# iTimeAfrica.net
KiCad netlist of a schematic drawn in Altium Designer
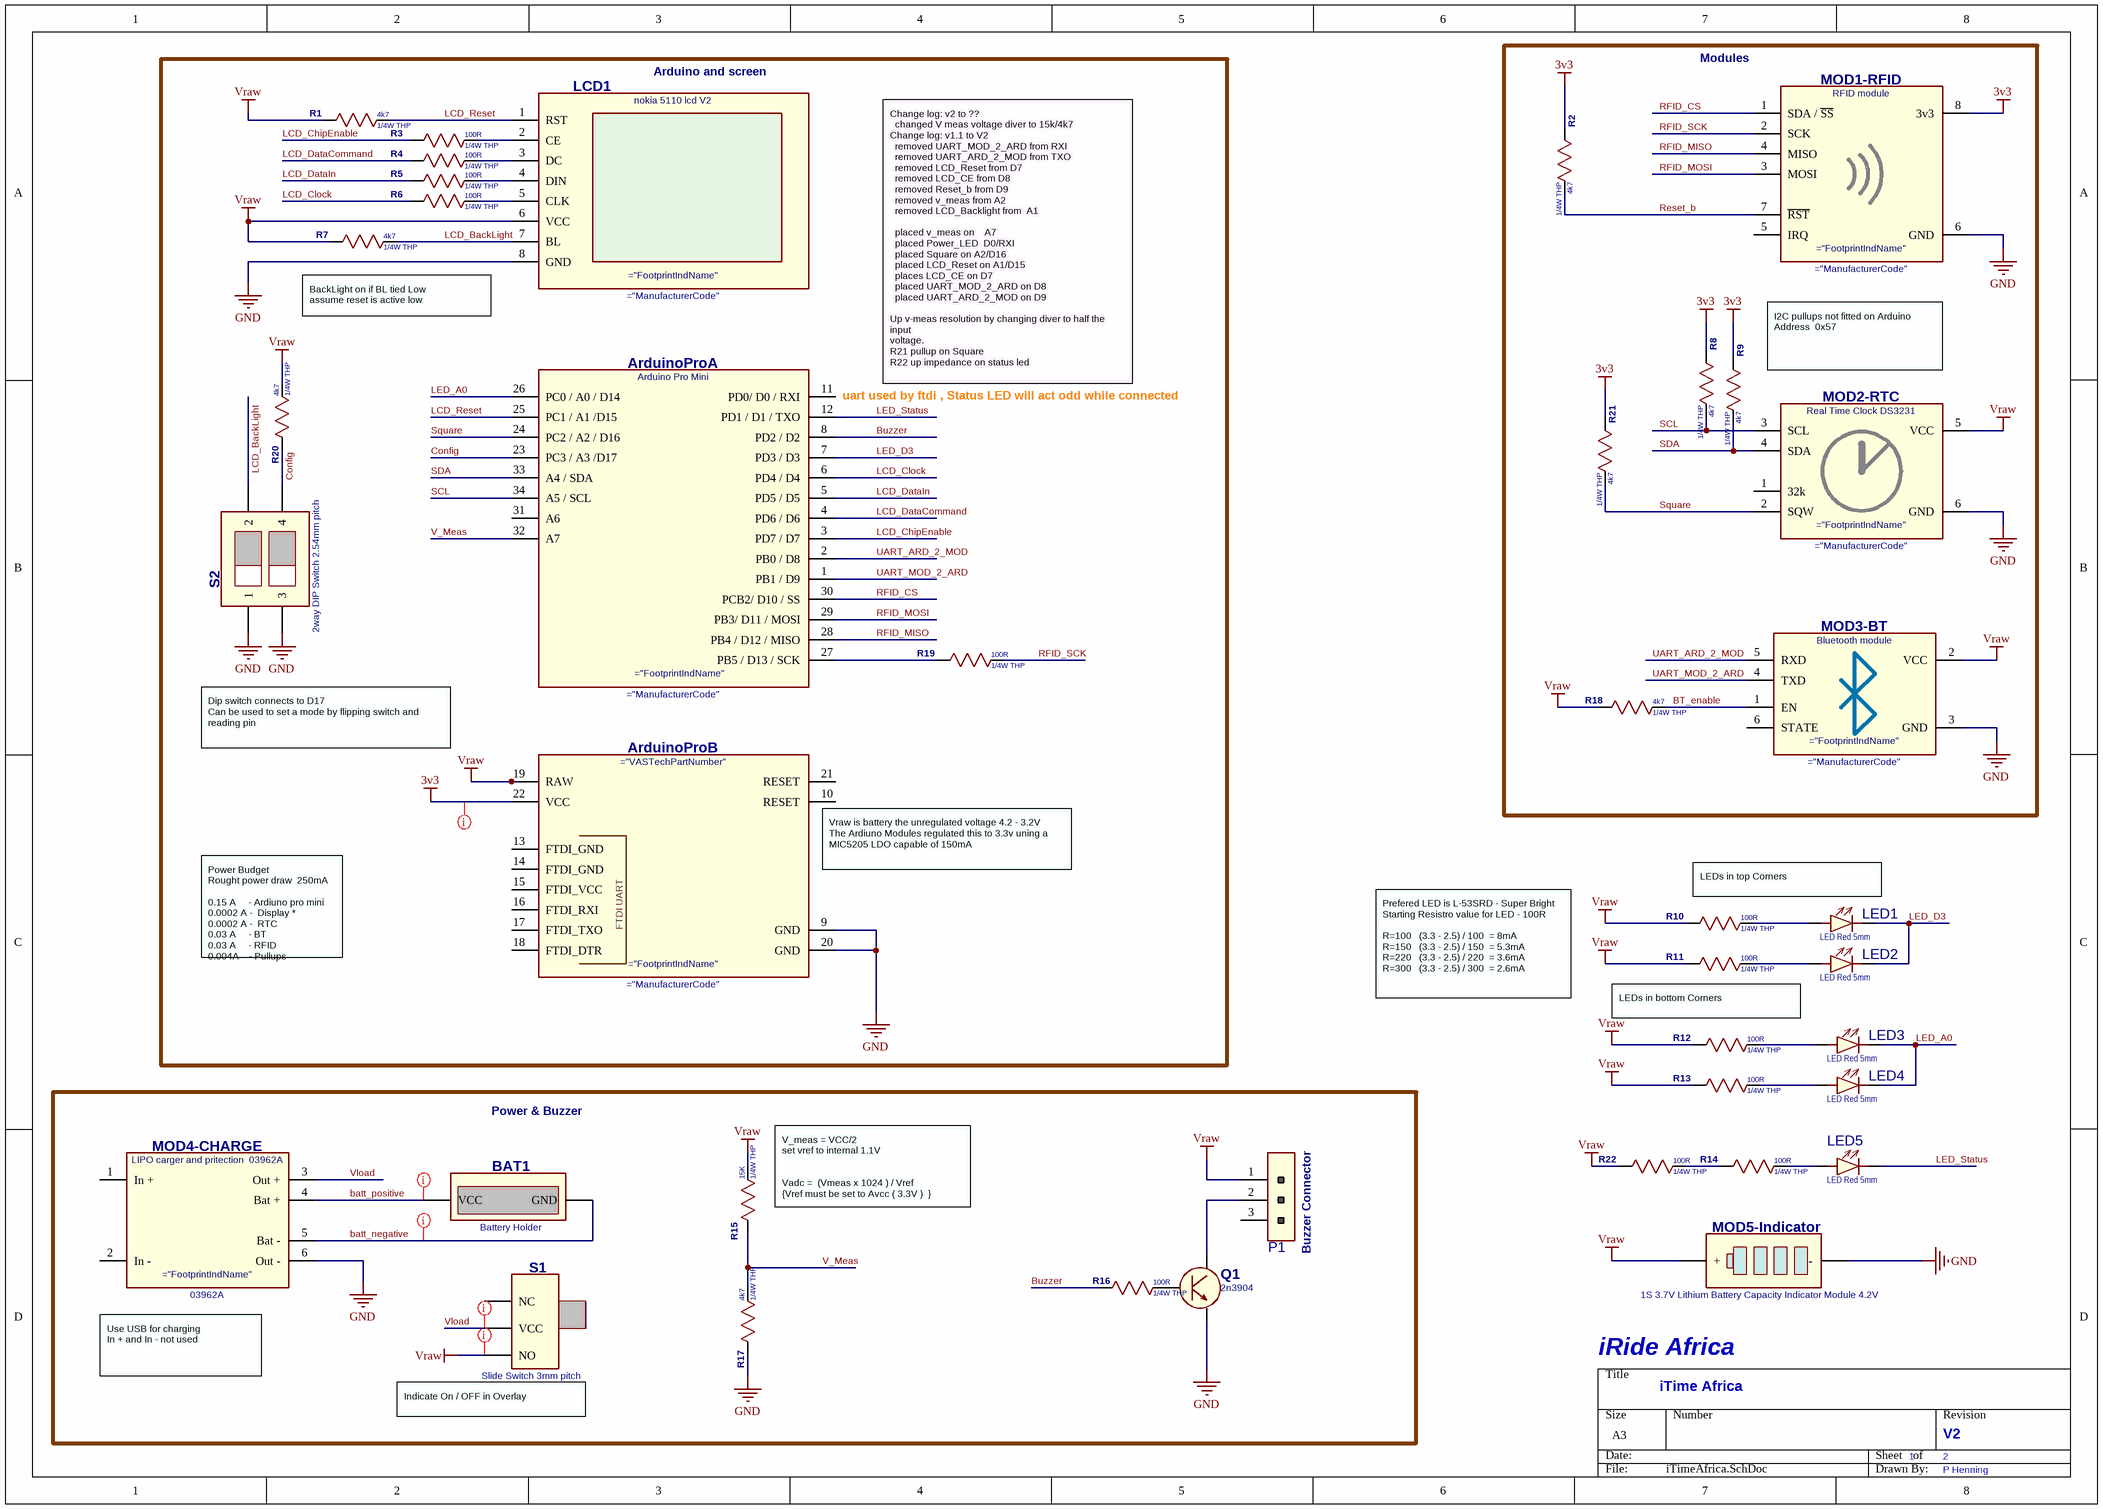
[diagram p0: iTimeAfrica.SchDoc]

(export (version "E")
  (design (tool "Eeschema 10.0.6"))
  (components
    (comp (ref "ArduinoPro")
      (value "Arduino Pro Mini")
      (footprint "ARDUINO PRO MINI v2 (NO FTDI)")
      (fields
        (field (name "MANUFACTURER") "SparkFun Electronics")
        (field (name "MANUFACTURERPARTNUMBER") "DEV-11113  (check this)")
      )
      (libsource (lib "Copy of Undero_Symbols_v7") (part "Arduino Pro Mini"))
    )
    (comp (ref "BAT1")
      (value "Battery Holder")
      (footprint "Battery Holder")
      (libsource (lib "Copy of Undero_Symbols_v7") (part "Battery Holder"))
    )
    (comp (ref "LCD1")
      (value "nokia 5110 lcd")
      (footprint "Nokia 5110 GLCD 84x48")
      (description "nokia 5110 lcd V2")
      (fields (field (name "MANUFACTURER") "unknown"))
      (libsource (lib "Copy of Undero_Symbols_v7") (part "nokia 5110 lcd V2"))
    )
    (comp (ref "LED1")
      (value "LED Red 5mm")
      (footprint "LED THL 5x9mm Vert")
      (description "Red LED, 5mm THP")
      (fields
        (field (name "MANUFACTURERPARTNUMBER") "L-53SR")
        (field (name "MANUFACTURER") "kingbright")
        (field (name "ATTRIBUTES") "LED Red 5mm")
      )
      (libsource (lib "Copy of Undero_Symbols_v7") (part "Red LED THP"))
    )
    (comp (ref "LED2")
      (value "LED Red 5mm")
      (footprint "LED THL 5x9mm Vert")
      (description "Red LED, 5mm THP")
      (fields
        (field (name "MANUFACTURERPARTNUMBER") "L-53SR")
        (field (name "MANUFACTURER") "kingbright")
        (field (name "ATTRIBUTES") "LED Red 5mm")
      )
      (libsource (lib "Copy of Undero_Symbols_v7") (part "Red LED THP"))
    )
    (comp (ref "LED3")
      (value "LED Red 5mm")
      (footprint "LED THL 5x9mm Vert")
      (description "Red LED, 5mm THP")
      (fields
        (field (name "MANUFACTURERPARTNUMBER") "L-53SR")
        (field (name "MANUFACTURER") "kingbright")
        (field (name "ATTRIBUTES") "LED Red 5mm")
      )
      (libsource (lib "Copy of Undero_Symbols_v7") (part "Red LED THP"))
    )
    (comp (ref "LED4")
      (value "LED Red 5mm")
      (footprint "LED THL 5x9mm Vert")
      (description "Red LED, 5mm THP")
      (fields
        (field (name "MANUFACTURERPARTNUMBER") "L-53SR")
        (field (name "MANUFACTURER") "kingbright")
        (field (name "ATTRIBUTES") "LED Red 5mm")
      )
      (libsource (lib "Copy of Undero_Symbols_v7") (part "Red LED THP"))
    )
    (comp (ref "LED5")
      (value "LED Red 5mm")
      (footprint "LED THL 5x9mm Vert")
      (description "Red LED, 5mm THP")
      (fields
        (field (name "MANUFACTURERPARTNUMBER") "L-53SR")
        (field (name "MANUFACTURER") "kingbright")
        (field (name "ATTRIBUTES") "LED Red 5mm")
      )
      (libsource (lib "Copy of Undero_Symbols_v7") (part "Red LED THP"))
    )
    (comp (ref "MOD1-RFID")
      (value "RFID module")
      (footprint "RFID-RC522 (2 MH)")
      (fields (field (name "MANUFACTURERPARTNUMBER") "RFID-RC533"))
      (libsource (lib "Copy of Undero_Symbols_v7") (part "RFID module"))
    )
    (comp (ref "MOD2-RTC")
      (value "Real Time Clock DS3231")
      (footprint "RTC DS3231 (2 MH)")
      (libsource (lib "Copy of Undero_Symbols_v7") (part "Real Time Clock DS3231"))
    )
    (comp (ref "MOD3-BT")
      (value "Bluetooth module")
      (footprint "BlueTooth Card")
      (libsource (lib "Copy of Undero_Symbols_v7") (part "Bluetooth module"))
    )
    (comp (ref "MOD4-CHARGE")
      (value "Real Time Clock DS3231")
      (footprint "Charger/protection")
      (description "LIPO carger and pritection  03962A")
      (fields (field (name "MANUFACTURERPARTNUMBER") "03962A"))
      (libsource (lib "iTimeAfrica_Symbol") (part "Charger / Protection"))
    )
    (comp (ref "MOD5-Indicator")
      (value "1S 3.7V Lithium Battery Capacity Indicator Module 4.2V")
      (footprint "Battery Indicator  single mouning hole")
      (libsource (lib "Copy of Undero_Symbols_v7") (part "Battery Indicator"))
    )
    (comp (ref "P1")
      (value "3 pin Screw Terminal 3.5mm")
      (footprint "3x1 Screw terminal 3.5mm")
      (fields (field (name "MANUFACTURERPARTNUMBER") "1984950") (field (name "MANUFACTURER") "RS"))
      (libsource (lib "Copy of Undero_Symbols_v7") (part "3 pin Screw Terminal 3.5mm"))
    )
    (comp (ref "Q1")
      (value "2n3904")
      (footprint "TO-92")
      (description "NPN Transistor")
      (fields (field (name "MANUFACTURER") "Fairchild") (field (name "ATTRIBUTES") "2n3904"))
      (libsource (lib "Copy of Undero_Symbols_v7") (part "NPN Transistor"))
    )
    (comp (ref "R1")
      (value "4k7")
      (footprint "Res 1/4W THP (4k7)")
      (description "Resistor")
      (fields (field (name "PACKAGE") "1/4W THP") (field (name "ATTRIBUTES") "4k7"))
      (libsource (lib "iTimeAfrica_Symbol") (part "4k7"))
    )
    (comp (ref "R2")
      (value "4k7")
      (footprint "Res 1/4W THP (4k7)")
      (description "Resistor")
      (fields (field (name "PACKAGE") "1/4W THP") (field (name "ATTRIBUTES") "4k7"))
      (libsource (lib "iTimeAfrica_Symbol") (part "4k7"))
    )
    (comp (ref "R3")
      (value "100R")
      (footprint "Res 1/4W THP (100R)")
      (description "Resistor")
      (fields (field (name "PACKAGE") "1/4W THP") (field (name "ATTRIBUTES") "100R"))
      (libsource (lib "iTimeAfrica_Symbol") (part "100R"))
    )
    (comp (ref "R4")
      (value "100R")
      (footprint "Res 1/4W THP (100R)")
      (description "Resistor")
      (fields (field (name "PACKAGE") "1/4W THP") (field (name "ATTRIBUTES") "100R"))
      (libsource (lib "iTimeAfrica_Symbol") (part "100R"))
    )
    (comp (ref "R5")
      (value "100R")
      (footprint "Res 1/4W THP (100R)")
      (description "Resistor")
      (fields (field (name "PACKAGE") "1/4W THP") (field (name "ATTRIBUTES") "100R"))
      (libsource (lib "iTimeAfrica_Symbol") (part "100R"))
    )
    (comp (ref "R6")
      (value "100R")
      (footprint "Res 1/4W THP (100R)")
      (description "Resistor")
      (fields (field (name "PACKAGE") "1/4W THP") (field (name "ATTRIBUTES") "100R"))
      (libsource (lib "iTimeAfrica_Symbol") (part "100R"))
    )
    (comp (ref "R7")
      (value "4k7")
      (footprint "Res 1/4W THP (4k7)")
      (description "Resistor")
      (fields (field (name "PACKAGE") "1/4W THP") (field (name "ATTRIBUTES") "4k7"))
      (libsource (lib "iTimeAfrica_Symbol") (part "4k7"))
    )
    (comp (ref "R8")
      (value "4k7")
      (footprint "Res 1/4W THP (4k7)")
      (description "Resistor")
      (fields (field (name "PACKAGE") "1/4W THP") (field (name "ATTRIBUTES") "4k7"))
      (libsource (lib "iTimeAfrica_Symbol") (part "4k7"))
    )
    (comp (ref "R9")
      (value "4k7")
      (footprint "Res 1/4W THP (4k7)")
      (description "Resistor")
      (fields (field (name "PACKAGE") "1/4W THP") (field (name "ATTRIBUTES") "4k7"))
      (libsource (lib "iTimeAfrica_Symbol") (part "4k7"))
    )
    (comp (ref "R10")
      (value "100R")
      (footprint "Res 1/4W THP (100R)")
      (description "Resistor")
      (fields (field (name "PACKAGE") "1/4W THP") (field (name "ATTRIBUTES") "100R"))
      (libsource (lib "iTimeAfrica_Symbol") (part "100R"))
    )
    (comp (ref "R11")
      (value "100R")
      (footprint "Res 1/4W THP (100R)")
      (description "Resistor")
      (fields (field (name "PACKAGE") "1/4W THP") (field (name "ATTRIBUTES") "100R"))
      (libsource (lib "iTimeAfrica_Symbol") (part "100R"))
    )
    (comp (ref "R12")
      (value "100R")
      (footprint "Res 1/4W THP (100R)")
      (description "Resistor")
      (fields (field (name "PACKAGE") "1/4W THP") (field (name "ATTRIBUTES") "100R"))
      (libsource (lib "iTimeAfrica_Symbol") (part "100R"))
    )
    (comp (ref "R13")
      (value "100R")
      (footprint "Res 1/4W THP (100R)")
      (description "Resistor")
      (fields (field (name "PACKAGE") "1/4W THP") (field (name "ATTRIBUTES") "100R"))
      (libsource (lib "iTimeAfrica_Symbol") (part "100R"))
    )
    (comp (ref "R14")
      (value "100R")
      (footprint "Res 1/4W THP (100R)")
      (description "Resistor")
      (fields (field (name "PACKAGE") "1/4W THP") (field (name "ATTRIBUTES") "100R"))
      (libsource (lib "iTimeAfrica_Symbol") (part "100R"))
    )
    (comp (ref "R15")
      (value "15K")
      (footprint "Res 1/4W THP")
      (description "Resistor")
      (fields (field (name "PACKAGE") "1/4W THP") (field (name "ATTRIBUTES") "15K"))
      (libsource (lib "iTimeAfrica_Symbol") (part "15K"))
    )
    (comp (ref "R16")
      (value "100R")
      (footprint "Res 1/4W THP (100R)")
      (description "Resistor")
      (fields (field (name "PACKAGE") "1/4W THP") (field (name "ATTRIBUTES") "100R"))
      (libsource (lib "iTimeAfrica_Symbol") (part "100R"))
    )
    (comp (ref "R17")
      (value "4k7")
      (footprint "Res 1/4W THP (4k7)")
      (description "Resistor")
      (fields (field (name "PACKAGE") "1/4W THP") (field (name "ATTRIBUTES") "4k7"))
      (libsource (lib "iTimeAfrica_Symbol") (part "4k7"))
    )
    (comp (ref "R18")
      (value "4k7")
      (footprint "Res 1/4W THP (4k7)")
      (description "Resistor")
      (fields (field (name "PACKAGE") "1/4W THP") (field (name "ATTRIBUTES") "4k7"))
      (libsource (lib "iTimeAfrica_Symbol") (part "4k7"))
    )
    (comp (ref "R19")
      (value "100R")
      (footprint "Res 1/4W THP (100R)")
      (description "Resistor")
      (fields (field (name "PACKAGE") "1/4W THP") (field (name "ATTRIBUTES") "100R"))
      (libsource (lib "iTimeAfrica_Symbol") (part "100R"))
    )
    (comp (ref "R20")
      (value "4k7")
      (footprint "Res 1/4W THP (4k7)")
      (description "Resistor")
      (fields (field (name "PACKAGE") "1/4W THP") (field (name "ATTRIBUTES") "4k7"))
      (libsource (lib "iTimeAfrica_Symbol") (part "4k7"))
    )
    (comp (ref "R21")
      (value "4k7")
      (footprint "Res 1/4W THP (4k7)")
      (description "Resistor")
      (fields (field (name "PACKAGE") "1/4W THP") (field (name "ATTRIBUTES") "4k7"))
      (libsource (lib "iTimeAfrica_Symbol") (part "4k7"))
    )
    (comp (ref "R22")
      (value "100R")
      (footprint "Res 1/4W THP (100R)")
      (description "Resistor")
      (fields (field (name "PACKAGE") "1/4W THP") (field (name "ATTRIBUTES") "100R"))
      (libsource (lib "iTimeAfrica_Symbol") (part "100R"))
    )
    (comp (ref "S1")
      (value "Slide Switch 3mm pitch")
      (footprint "Slide Switch 3mm")
      (fields (field (name "MANUFACTURER") "Arcolectric Corporation"))
      (libsource (lib "Copy of Undero_Symbols_v7") (part "Slide Switch 3mm pitch"))
    )
    (comp (ref "S2")
      (value "2x DIP Switch 2.54mm pitch")
      (footprint "2way DIP switch")
      (description "2way DIP Switch 2.54mm pitch")
      (fields
        (field (name "MANUFACTURER") "Arcolectric Corporation")
        (field (name "MANUFACTURERPARTNUMBER") "KTS02E")
      )
      (libsource (lib "Copy of Undero_Symbols_v7") (part "2way DIP Switch 2.54mm pitch"))
    )
  )
  (nets
    (net (code "1") (name "/BT_enable") (class "Default")
      (node (ref "MOD3-BT") (pin "1") (pinfunction "EN_1") (pintype "passive"))
      (node (ref "R18") (pin "2") (pinfunction "2_2") (pintype "passive"))
    )
    (net (code "2") (name "/Buzzer") (class "Default")
      (node (ref "ArduinoPro") (pin "8") (pinfunction "PD2_/_D2_8") (pintype "passive"))
      (node (ref "R16") (pin "1") (pinfunction "1_1") (pintype "passive"))
    )
    (net (code "3") (name "/Config") (class "Default")
      (node (ref "ArduinoPro") (pin "23") (pinfunction "PC3_/_A3_/D17_23") (pintype "passive"))
      (node (ref "R20") (pin "1") (pinfunction "1_1") (pintype "passive"))
      (node (ref "S2") (pin "4") (pinfunction "4_4") (pintype "passive"))
    )
    (net (code "4") (name "/LCD_BackLight") (class "Default")
      (node (ref "LCD1") (pin "7") (pinfunction "BL_7") (pintype "passive"))
      (node (ref "R7") (pin "2") (pinfunction "2_2") (pintype "passive"))
      (node (ref "S2") (pin "2") (pinfunction "2_2") (pintype "passive"))
    )
    (net (code "5") (name "/LCD_ChipEnable") (class "Default")
      (node (ref "ArduinoPro") (pin "3") (pinfunction "PD7_/_D7_3") (pintype "passive"))
      (node (ref "R3") (pin "1") (pinfunction "1_1") (pintype "passive"))
    )
    (net (code "6") (name "/LCD_Clock") (class "Default")
      (node (ref "ArduinoPro") (pin "6") (pinfunction "PD4_/_D4_6") (pintype "passive"))
      (node (ref "R6") (pin "1") (pinfunction "1_1") (pintype "passive"))
    )
    (net (code "7") (name "/LCD_DataCommand") (class "Default")
      (node (ref "ArduinoPro") (pin "4") (pinfunction "PD6_/_D6_4") (pintype "passive"))
      (node (ref "R4") (pin "1") (pinfunction "1_1") (pintype "passive"))
    )
    (net (code "8") (name "/LCD_DataIn") (class "Default")
      (node (ref "ArduinoPro") (pin "5") (pinfunction "PD5_/_D5_5") (pintype "passive"))
      (node (ref "R5") (pin "1") (pinfunction "1_1") (pintype "passive"))
    )
    (net (code "9") (name "/LCD_Reset") (class "Default")
      (node (ref "ArduinoPro") (pin "25") (pinfunction "PC1_/_A1_/D15_25") (pintype "passive"))
      (node (ref "LCD1") (pin "1") (pinfunction "RST_1") (pintype "passive"))
      (node (ref "R1") (pin "2") (pinfunction "2_2") (pintype "passive"))
    )
    (net (code "10") (name "/LED_A0") (class "Default")
      (node (ref "ArduinoPro") (pin "26") (pinfunction "PC0_/_A0_/_D14_26") (pintype "passive"))
      (node (ref "LED3") (pin "2") (pinfunction "C_2") (pintype "passive"))
      (node (ref "LED4") (pin "2") (pinfunction "C_2") (pintype "passive"))
    )
    (net (code "11") (name "/LED_D3") (class "Default")
      (node (ref "ArduinoPro") (pin "7") (pinfunction "PD3_/_D3_7") (pintype "passive"))
      (node (ref "LED1") (pin "2") (pinfunction "C_2") (pintype "passive"))
      (node (ref "LED2") (pin "2") (pinfunction "C_2") (pintype "passive"))
    )
    (net (code "12") (name "/LED_Status") (class "Default")
      (node (ref "ArduinoPro") (pin "12") (pinfunction "PD1_/_D1_/_TXO_12") (pintype "passive"))
      (node (ref "LED5") (pin "2") (pinfunction "C_2") (pintype "passive"))
    )
    (net (code "13") (name "/RFID_CS") (class "Default")
      (node (ref "ArduinoPro") (pin "30") (pinfunction "PCB2/_D10_/_SS_30") (pintype "passive"))
      (node (ref "MOD1-RFID") (pin "1") (pinfunction "SDA_/_~{SS}_1") (pintype "passive"))
    )
    (net (code "14") (name "/RFID_MISO") (class "Default")
      (node (ref "ArduinoPro") (pin "28") (pinfunction "PB4_/_D12_/_MISO_28") (pintype "passive"))
      (node (ref "MOD1-RFID") (pin "4") (pinfunction "MISO_4") (pintype "passive"))
    )
    (net (code "15") (name "/RFID_MOSI") (class "Default")
      (node (ref "ArduinoPro") (pin "29") (pinfunction "PB3/_D11_/_MOSI_29") (pintype "passive"))
      (node (ref "MOD1-RFID") (pin "3") (pinfunction "MOSI_3") (pintype "passive"))
    )
    (net (code "16") (name "/RFID_SCK") (class "Default")
      (node (ref "MOD1-RFID") (pin "2") (pinfunction "SCK_2") (pintype "passive"))
      (node (ref "R19") (pin "2") (pinfunction "2_2") (pintype "passive"))
    )
    (net (code "17") (name "/Reset_b") (class "Default")
      (node (ref "MOD1-RFID") (pin "7") (pinfunction "RST_7") (pintype "passive"))
      (node (ref "R2") (pin "2") (pinfunction "2_2") (pintype "passive"))
    )
    (net (code "18") (name "/SCL") (class "Default")
      (node (ref "ArduinoPro") (pin "34") (pinfunction "A5_/_SCL_34") (pintype "passive"))
      (node (ref "MOD2-RTC") (pin "3") (pinfunction "SCL_3") (pintype "passive"))
      (node (ref "R8") (pin "2") (pinfunction "2_2") (pintype "passive"))
    )
    (net (code "19") (name "/SDA") (class "Default")
      (node (ref "ArduinoPro") (pin "33") (pinfunction "A4_/_SDA_33") (pintype "passive"))
      (node (ref "MOD2-RTC") (pin "4") (pinfunction "SDA_4") (pintype "passive"))
      (node (ref "R9") (pin "2") (pinfunction "2_2") (pintype "passive"))
    )
    (net (code "20") (name "/Square") (class "Default")
      (node (ref "ArduinoPro") (pin "24") (pinfunction "PC2_/_A2_/_D16_24") (pintype "passive"))
      (node (ref "MOD2-RTC") (pin "2") (pinfunction "SQW_2") (pintype "passive"))
      (node (ref "R21") (pin "2") (pinfunction "2_2") (pintype "passive"))
    )
    (net (code "21") (name "/UART_ARD_2_MOD") (class "Default")
      (node (ref "ArduinoPro") (pin "2") (pinfunction "PB0_/_D8_2") (pintype "passive"))
      (node (ref "MOD3-BT") (pin "5") (pinfunction "RXD_5") (pintype "passive"))
    )
    (net (code "22") (name "/UART_MOD_2_ARD") (class "Default")
      (node (ref "ArduinoPro") (pin "1") (pinfunction "PB1_/_D9_1") (pintype "passive"))
      (node (ref "MOD3-BT") (pin "4") (pinfunction "TXD_4") (pintype "passive"))
    )
    (net (code "23") (name "/V_Meas") (class "Default")
      (node (ref "ArduinoPro") (pin "32") (pinfunction "A7_32") (pintype "passive"))
      (node (ref "R15") (pin "1") (pinfunction "1_1") (pintype "passive"))
      (node (ref "R17") (pin "2") (pinfunction "2_2") (pintype "passive"))
    )
    (net (code "24") (name "/Vload") (class "Default")
      (node (ref "MOD4-CHARGE") (pin "3") (pinfunction "Out_+_3") (pintype "passive"))
      (node (ref "S1") (pin "2") (pinfunction "VCC_2") (pintype "passive"))
    )
    (net (code "25") (name "/batt_negative") (class "Default")
      (node (ref "BAT1") (pin "2") (pinfunction "GND_2") (pintype "passive"))
      (node (ref "MOD4-CHARGE") (pin "5") (pinfunction "Bat_-_5") (pintype "passive"))
    )
    (net (code "26") (name "/batt_positive") (class "Default")
      (node (ref "BAT1") (pin "1") (pinfunction "VCC_1") (pintype "passive"))
      (node (ref "MOD4-CHARGE") (pin "4") (pinfunction "Bat_+_4") (pintype "passive"))
    )
    (net (code "27") (name "3v3") (class "Default")
      (node (ref "ArduinoPro") (pin "22") (pinfunction "VCC_22") (pintype "passive"))
      (node (ref "MOD1-RFID") (pin "8") (pinfunction "3v3_8") (pintype "passive"))
      (node (ref "R2") (pin "1") (pinfunction "1_1") (pintype "passive"))
      (node (ref "R21") (pin "1") (pinfunction "1_1") (pintype "passive"))
      (node (ref "R8") (pin "1") (pinfunction "1_1") (pintype "passive"))
      (node (ref "R9") (pin "1") (pinfunction "1_1") (pintype "passive"))
    )
    (net (code "28") (name "GND") (class "Default")
      (node (ref "ArduinoPro") (pin "20") (pinfunction "GND_20") (pintype "passive"))
      (node (ref "ArduinoPro") (pin "9") (pinfunction "GND_9") (pintype "passive"))
      (node (ref "LCD1") (pin "8") (pinfunction "GND_8") (pintype "passive"))
      (node (ref "MOD1-RFID") (pin "6") (pinfunction "GND_6") (pintype "passive"))
      (node (ref "MOD2-RTC") (pin "6") (pinfunction "GND_6") (pintype "passive"))
      (node (ref "MOD3-BT") (pin "3") (pinfunction "GND_3") (pintype "passive"))
      (node (ref "MOD4-CHARGE") (pin "6") (pinfunction "Out_-_6") (pintype "passive"))
      (node (ref "MOD5-Indicator") (pin "2") (pinfunction "-_2") (pintype "passive"))
      (node (ref "Q1") (pin "3") (pinfunction "E_3") (pintype "passive"))
      (node (ref "R17") (pin "1") (pinfunction "1_1") (pintype "passive"))
      (node (ref "S2") (pin "1") (pinfunction "1_1") (pintype "passive"))
      (node (ref "S2") (pin "3") (pinfunction "3_3") (pintype "passive"))
    )
    (net (code "29") (name "Net-(ArduinoProA-PB5_{slash}_D13_{slash}_SCK)") (class "Default")
      (node (ref "ArduinoPro") (pin "27") (pinfunction "PB5_/_D13_/_SCK_27") (pintype "passive"))
      (node (ref "R19") (pin "1") (pinfunction "1_1") (pintype "passive"))
    )
    (net (code "30") (name "Net-(LCD1-CE)") (class "Default")
      (node (ref "LCD1") (pin "2") (pinfunction "CE_2") (pintype "passive"))
      (node (ref "R3") (pin "2") (pinfunction "2_2") (pintype "passive"))
    )
    (net (code "31") (name "Net-(LCD1-CLK)") (class "Default")
      (node (ref "LCD1") (pin "5") (pinfunction "CLK_5") (pintype "passive"))
      (node (ref "R6") (pin "2") (pinfunction "2_2") (pintype "passive"))
    )
    (net (code "32") (name "Net-(LCD1-DC)") (class "Default")
      (node (ref "LCD1") (pin "3") (pinfunction "DC_3") (pintype "passive"))
      (node (ref "R4") (pin "2") (pinfunction "2_2") (pintype "passive"))
    )
    (net (code "33") (name "Net-(LCD1-DIN)") (class "Default")
      (node (ref "LCD1") (pin "4") (pinfunction "DIN_4") (pintype "passive"))
      (node (ref "R5") (pin "2") (pinfunction "2_2") (pintype "passive"))
    )
    (net (code "34") (name "Net-(LED1-A)") (class "Default")
      (node (ref "LED1") (pin "1") (pinfunction "A_1") (pintype "passive"))
      (node (ref "R10") (pin "2") (pinfunction "2_2") (pintype "passive"))
    )
    (net (code "35") (name "Net-(LED2-A)") (class "Default")
      (node (ref "LED2") (pin "1") (pinfunction "A_1") (pintype "passive"))
      (node (ref "R11") (pin "2") (pinfunction "2_2") (pintype "passive"))
    )
    (net (code "36") (name "Net-(LED3-A)") (class "Default")
      (node (ref "LED3") (pin "1") (pinfunction "A_1") (pintype "passive"))
      (node (ref "R12") (pin "2") (pinfunction "2_2") (pintype "passive"))
    )
    (net (code "37") (name "Net-(LED4-A)") (class "Default")
      (node (ref "LED4") (pin "1") (pinfunction "A_1") (pintype "passive"))
      (node (ref "R13") (pin "2") (pinfunction "2_2") (pintype "passive"))
    )
    (net (code "38") (name "Net-(LED5-A)") (class "Default")
      (node (ref "LED5") (pin "1") (pinfunction "A_1") (pintype "passive"))
      (node (ref "R14") (pin "2") (pinfunction "2_2") (pintype "passive"))
    )
    (net (code "39") (name "Net-(Q1-B)") (class "Default")
      (node (ref "Q1") (pin "2") (pinfunction "B_2") (pintype "passive"))
      (node (ref "R16") (pin "2") (pinfunction "2_2") (pintype "passive"))
    )
    (net (code "40") (name "Net-(Q1-C)") (class "Default")
      (node (ref "P1") (pin "2") (pinfunction "2_2") (pintype "passive"))
      (node (ref "Q1") (pin "1") (pinfunction "C_1") (pintype "passive"))
    )
    (net (code "41") (name "Net-(R14-Pad1)") (class "Default")
      (node (ref "R14") (pin "1") (pinfunction "1_1") (pintype "passive"))
      (node (ref "R22") (pin "2") (pinfunction "2_2") (pintype "passive"))
    )
    (net (code "42") (name "Vraw") (class "Default")
      (node (ref "ArduinoPro") (pin "19") (pinfunction "RAW_19") (pintype "passive"))
      (node (ref "LCD1") (pin "6") (pinfunction "VCC_6") (pintype "passive"))
      (node (ref "MOD2-RTC") (pin "5") (pinfunction "VCC_5") (pintype "passive"))
      (node (ref "MOD3-BT") (pin "2") (pinfunction "VCC_2") (pintype "passive"))
      (node (ref "MOD5-Indicator") (pin "1") (pinfunction "+_1") (pintype "passive"))
      (node (ref "P1") (pin "1") (pinfunction "1_1") (pintype "passive"))
      (node (ref "R1") (pin "1") (pinfunction "1_1") (pintype "passive"))
      (node (ref "R10") (pin "1") (pinfunction "1_1") (pintype "passive"))
      (node (ref "R11") (pin "1") (pinfunction "1_1") (pintype "passive"))
      (node (ref "R12") (pin "1") (pinfunction "1_1") (pintype "passive"))
      (node (ref "R13") (pin "1") (pinfunction "1_1") (pintype "passive"))
      (node (ref "R15") (pin "2") (pinfunction "2_2") (pintype "passive"))
      (node (ref "R18") (pin "1") (pinfunction "1_1") (pintype "passive"))
      (node (ref "R20") (pin "2") (pinfunction "2_2") (pintype "passive"))
      (node (ref "R22") (pin "1") (pinfunction "1_1") (pintype "passive"))
      (node (ref "R7") (pin "1") (pinfunction "1_1") (pintype "passive"))
      (node (ref "S1") (pin "3") (pinfunction "NO_3") (pintype "passive"))
    )
    (net (code "43") (name "unconnected-(ArduinoProA-A6-Pad31)") (class "Default")
      (node (ref "ArduinoPro") (pin "31") (pinfunction "A6_31") (pintype "passive"))
    )
    (net (code "44") (name "unconnected-(ArduinoProA-PD0{slash}_D0_{slash}_RXI-Pad11)") (class "Default")
      (node (ref "ArduinoPro") (pin "11") (pinfunction "PD0/_D0_/_RXI_11") (pintype "passive"))
    )
    (net (code "45") (name "unconnected-(ArduinoProB-FTDI_DTR-Pad18)") (class "Default")
      (node (ref "ArduinoPro") (pin "18") (pinfunction "FTDI_DTR_18") (pintype "passive"))
    )
    (net (code "46") (name "unconnected-(ArduinoProB-FTDI_GND-Pad13)") (class "Default")
      (node (ref "ArduinoPro") (pin "13") (pinfunction "FTDI_GND_13") (pintype "passive"))
    )
    (net (code "47") (name "unconnected-(ArduinoProB-FTDI_GND-Pad14)") (class "Default")
      (node (ref "ArduinoPro") (pin "14") (pinfunction "FTDI_GND_14") (pintype "passive"))
    )
    (net (code "48") (name "unconnected-(ArduinoProB-FTDI_RXI-Pad16)") (class "Default")
      (node (ref "ArduinoPro") (pin "16") (pinfunction "FTDI_RXI_16") (pintype "passive"))
    )
    (net (code "49") (name "unconnected-(ArduinoProB-FTDI_TXO-Pad17)") (class "Default")
      (node (ref "ArduinoPro") (pin "17") (pinfunction "FTDI_TXO_17") (pintype "passive"))
    )
    (net (code "50") (name "unconnected-(ArduinoProB-FTDI_VCC-Pad15)") (class "Default")
      (node (ref "ArduinoPro") (pin "15") (pinfunction "FTDI_VCC_15") (pintype "passive"))
    )
    (net (code "51") (name "unconnected-(ArduinoProB-RESET-Pad10)") (class "Default")
      (node (ref "ArduinoPro") (pin "10") (pinfunction "RESET_10") (pintype "passive"))
    )
    (net (code "52") (name "unconnected-(ArduinoProB-RESET-Pad21)") (class "Default")
      (node (ref "ArduinoPro") (pin "21") (pinfunction "RESET_21") (pintype "passive"))
    )
    (net (code "53") (name "unconnected-(MOD1-RFID-IRQ-Pad5)") (class "Default")
      (node (ref "MOD1-RFID") (pin "5") (pinfunction "IRQ_5") (pintype "passive"))
    )
    (net (code "54") (name "unconnected-(MOD2-RTC-32k-Pad1)") (class "Default")
      (node (ref "MOD2-RTC") (pin "1") (pinfunction "32k_1") (pintype "passive"))
    )
    (net (code "55") (name "unconnected-(MOD3-BT-STATE-Pad6)") (class "Default")
      (node (ref "MOD3-BT") (pin "6") (pinfunction "STATE_6") (pintype "passive"))
    )
    (net (code "56") (name "unconnected-(MOD4-CHARGE-In_+-Pad1)") (class "Default")
      (node (ref "MOD4-CHARGE") (pin "1") (pinfunction "In_+_1") (pintype "passive"))
    )
    (net (code "57") (name "unconnected-(MOD4-CHARGE-In_--Pad2)") (class "Default")
      (node (ref "MOD4-CHARGE") (pin "2") (pinfunction "In_-_2") (pintype "passive"))
    )
    (net (code "58") (name "unconnected-(P1-Pad3)") (class "Default")
      (node (ref "P1") (pin "3") (pinfunction "3_3") (pintype "passive"))
    )
    (net (code "59") (name "unconnected-(S1-NC-Pad1)") (class "Default")
      (node (ref "S1") (pin "1") (pinfunction "NC_1") (pintype "passive"))
    )
  )
)
